# 1_IIP_Charge.net
KiCad netlist of a schematic drawn in Altium Designer
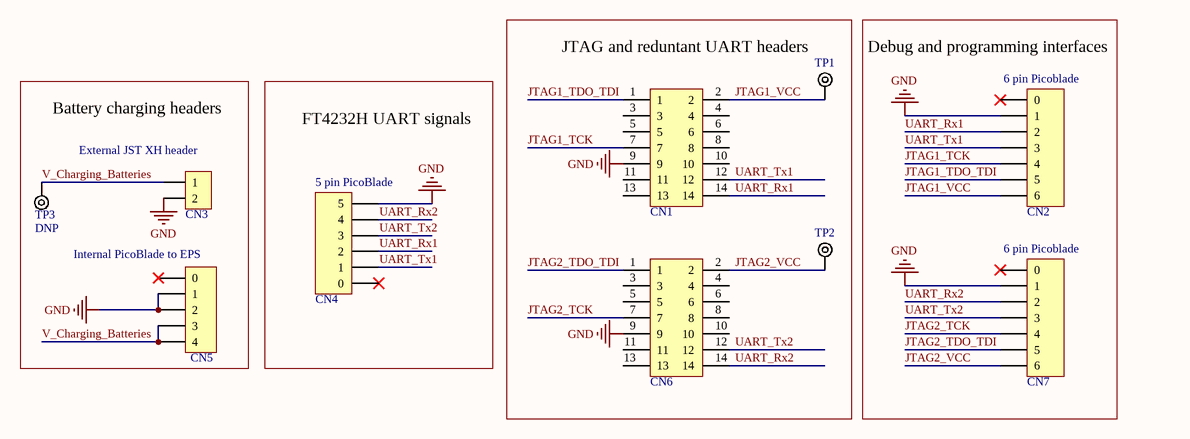
[diagram p0: 1_IIP_Charge.SchDoc]

(export (version "E")
  (design (tool "Eeschema 10.0.6"))
  (components
    (comp (ref "CN1")
      (value "7 POS dual line Pin Header 2.54mm")
      (footprint "CONN HEADER VERT 14POS 2.54MM")
      (description "Headers & Wire Housings 07+07 DIL VERTICAL PIN HEADER GOLD HT")
      (fields (field (name "MANUFACTURER") "Harwin") (field (name "MANUFACTURER PART NUMBER") "M20-9980745"))
      (libsource (lib "IB_floripasat2") (part "M20-9980745"))
    )
    (comp (ref "CN2")
      (value "6 pin Picoblade")
      (footprint "PICO BLADE 0533980671")
      (description "1.25mm Pitch PicoBlade™ Header, Surface Mount, Vertical, 6 Circuits")
      (fields (field (name "MANUFACTURER") "Molex") (field (name "MANUFACTURER PART NUMBER") "53398-0671"))
      (libsource (lib "IB_floripasat2") (part "53398-0671"))
    )
    (comp (ref "CN3")
      (value "JST 2 position header 2.5mm")
      (footprint "B2B-XH-A-M(LF)(SN)")
      (description "CONN HEADER TOP 2POS 2.5MM GRN")
      (fields
        (field (name "MANUFACTURER") "JST")
        (field (name "MANUFACTURER PART NUMBER") "B2B-XH-A-M(LF)(SN)")
      )
      (libsource (lib "IB_floripasat2") (part "B2B-XH-A-M(LF)(SN)"))
    )
    (comp (ref "CN4")
      (value "5 pin PicoBlade")
      (footprint "PICO BLADE 0533980571")
      (description "Wire-To-Board Connector, Vertical, PicoBlade 53398 Series, Surface Mount, Header, 5, 1.25 mm")
      (fields (field (name "MANUFACTURER") "Molex") (field (name "MANUFACTURER PART NUMBER") "53398-0571"))
      (libsource (lib "IB_floripasat2") (part "53398-0571"))
    )
    (comp (ref "CN5")
      (value "4 pin Picoblade")
      (footprint "PICO BLADE 0533980471")
      (description "Conn Wire to Board HDR 4 POS 1.25mm Solder ST SMD Embossed T/R")
      (fields (field (name "MANUFACTURER") "Molex"))
      (libsource (lib "IB_floripasat2") (part "0533980471"))
    )
    (comp (ref "CN6")
      (value "7 POS dual line Pin Header 2.54mm")
      (footprint "CONN HEADER VERT 14POS 2.54MM")
      (description "Headers & Wire Housings 07+07 DIL VERTICAL PIN HEADER GOLD HT")
      (fields (field (name "MANUFACTURER") "Harwin") (field (name "MANUFACTURER PART NUMBER") "M20-9980745"))
      (libsource (lib "IB_floripasat2") (part "M20-9980745"))
    )
    (comp (ref "CN7")
      (value "6 pin Picoblade")
      (footprint "PICO BLADE 0533980671")
      (description "1.25mm Pitch PicoBlade™ Header, Surface Mount, Vertical, 6 Circuits")
      (fields (field (name "MANUFACTURER") "Molex") (field (name "MANUFACTURER PART NUMBER") "53398-0671"))
      (libsource (lib "IB_floripasat2") (part "53398-0671"))
    )
    (comp (ref "TP1")
      (value "DNP")
      (footprint "TEST POINT PTH")
      (description "TEST POINT PAD")
      (libsource (lib "IB_floripasat2") (part "Test Point PTH"))
    )
    (comp (ref "TP2")
      (value "DNP")
      (footprint "TEST POINT PTH")
      (description "TEST POINT PAD")
      (libsource (lib "IB_floripasat2") (part "Test Point PTH"))
    )
    (comp (ref "TP3")
      (value "DNP")
      (footprint "TEST POINT PTH")
      (description "TEST POINT PAD")
      (libsource (lib "IB_floripasat2") (part "Test Point PTH"))
    )
  )
  (nets
    (net (code "1") (name "/JTAG1_TCK") (class "Default")
      (node (ref "CN1") (pin "7") (pinfunction "7_7") (pintype "passive"))
      (node (ref "CN2") (pin "4") (pinfunction "4_4") (pintype "passive"))
    )
    (net (code "2") (name "/JTAG1_TDO_TDI") (class "Default")
      (node (ref "CN1") (pin "1") (pinfunction "1_1") (pintype "passive"))
      (node (ref "CN2") (pin "5") (pinfunction "5_5") (pintype "passive"))
    )
    (net (code "3") (name "/JTAG1_VCC") (class "Default")
      (node (ref "CN1") (pin "2") (pinfunction "2_2") (pintype "passive"))
      (node (ref "CN2") (pin "6") (pinfunction "6_6") (pintype "passive"))
      (node (ref "TP1") (pin "1") (pinfunction "1_1") (pintype "passive"))
    )
    (net (code "4") (name "/JTAG2_TCK") (class "Default")
      (node (ref "CN6") (pin "7") (pinfunction "7_7") (pintype "passive"))
      (node (ref "CN7") (pin "4") (pinfunction "4_4") (pintype "passive"))
    )
    (net (code "5") (name "/JTAG2_TDO_TDI") (class "Default")
      (node (ref "CN6") (pin "1") (pinfunction "1_1") (pintype "passive"))
      (node (ref "CN7") (pin "5") (pinfunction "5_5") (pintype "passive"))
    )
    (net (code "6") (name "/JTAG2_VCC") (class "Default")
      (node (ref "CN6") (pin "2") (pinfunction "2_2") (pintype "passive"))
      (node (ref "CN7") (pin "6") (pinfunction "6_6") (pintype "passive"))
      (node (ref "TP2") (pin "1") (pinfunction "1_1") (pintype "passive"))
    )
    (net (code "7") (name "/UART_Rx1") (class "Default")
      (node (ref "CN1") (pin "14") (pinfunction "14_14") (pintype "passive"))
      (node (ref "CN2") (pin "2") (pinfunction "2_2") (pintype "passive"))
      (node (ref "CN4") (pin "2") (pinfunction "2_2") (pintype "passive"))
    )
    (net (code "8") (name "/UART_Rx2") (class "Default")
      (node (ref "CN4") (pin "4") (pinfunction "4_4") (pintype "passive"))
      (node (ref "CN6") (pin "14") (pinfunction "14_14") (pintype "passive"))
      (node (ref "CN7") (pin "2") (pinfunction "2_2") (pintype "passive"))
    )
    (net (code "9") (name "/UART_Tx1") (class "Default")
      (node (ref "CN1") (pin "12") (pinfunction "12_12") (pintype "passive"))
      (node (ref "CN2") (pin "3") (pinfunction "3_3") (pintype "passive"))
      (node (ref "CN4") (pin "1") (pinfunction "1_1") (pintype "passive"))
    )
    (net (code "10") (name "/UART_Tx2") (class "Default")
      (node (ref "CN4") (pin "3") (pinfunction "3_3") (pintype "passive"))
      (node (ref "CN6") (pin "12") (pinfunction "12_12") (pintype "passive"))
      (node (ref "CN7") (pin "3") (pinfunction "3_3") (pintype "passive"))
    )
    (net (code "11") (name "/V_Charging_Batteries") (class "Default")
      (node (ref "CN3") (pin "1") (pinfunction "1_1") (pintype "passive"))
      (node (ref "CN5") (pin "3") (pinfunction "3_3") (pintype "passive"))
      (node (ref "CN5") (pin "4") (pinfunction "4_4") (pintype "passive"))
      (node (ref "TP3") (pin "1") (pinfunction "1_1") (pintype "passive"))
    )
    (net (code "12") (name "GND") (class "Default")
      (node (ref "CN1") (pin "9") (pinfunction "9_9") (pintype "passive"))
      (node (ref "CN2") (pin "1") (pinfunction "1_1") (pintype "passive"))
      (node (ref "CN3") (pin "2") (pinfunction "2_2") (pintype "passive"))
      (node (ref "CN4") (pin "5") (pinfunction "5_5") (pintype "passive"))
      (node (ref "CN5") (pin "1") (pinfunction "1_1") (pintype "passive"))
      (node (ref "CN5") (pin "2") (pinfunction "2_2") (pintype "passive"))
      (node (ref "CN6") (pin "9") (pinfunction "9_9") (pintype "passive"))
      (node (ref "CN7") (pin "1") (pinfunction "1_1") (pintype "passive"))
    )
    (net (code "13") (name "unconnected-(CN1-Pad3)") (class "Default")
      (node (ref "CN1") (pin "3") (pinfunction "3_3") (pintype "passive"))
    )
    (net (code "14") (name "unconnected-(CN1-Pad4)") (class "Default")
      (node (ref "CN1") (pin "4") (pinfunction "4_4") (pintype "passive"))
    )
    (net (code "15") (name "unconnected-(CN1-Pad5)") (class "Default")
      (node (ref "CN1") (pin "5") (pinfunction "5_5") (pintype "passive"))
    )
    (net (code "16") (name "unconnected-(CN1-Pad6)") (class "Default")
      (node (ref "CN1") (pin "6") (pinfunction "6_6") (pintype "passive"))
    )
    (net (code "17") (name "unconnected-(CN1-Pad8)") (class "Default")
      (node (ref "CN1") (pin "8") (pinfunction "8_8") (pintype "passive"))
    )
    (net (code "18") (name "unconnected-(CN1-Pad10)") (class "Default")
      (node (ref "CN1") (pin "10") (pinfunction "10_10") (pintype "passive"))
    )
    (net (code "19") (name "unconnected-(CN1-Pad11)") (class "Default")
      (node (ref "CN1") (pin "11") (pinfunction "11_11") (pintype "passive"))
    )
    (net (code "20") (name "unconnected-(CN1-Pad13)") (class "Default")
      (node (ref "CN1") (pin "13") (pinfunction "13_13") (pintype "passive"))
    )
    (net (code "21") (name "unconnected-(CN2-Pad0)") (class "Default")
      (node (ref "CN2") (pin "0") (pinfunction "0_0") (pintype "passive+no_connect"))
    )
    (net (code "22") (name "unconnected-(CN4-Pad0)") (class "Default")
      (node (ref "CN4") (pin "0") (pinfunction "0_0") (pintype "passive+no_connect"))
    )
    (net (code "23") (name "unconnected-(CN5-Pad0)") (class "Default")
      (node (ref "CN5") (pin "0") (pinfunction "0_0") (pintype "passive+no_connect"))
    )
    (net (code "24") (name "unconnected-(CN6-Pad3)") (class "Default")
      (node (ref "CN6") (pin "3") (pinfunction "3_3") (pintype "passive"))
    )
    (net (code "25") (name "unconnected-(CN6-Pad4)") (class "Default")
      (node (ref "CN6") (pin "4") (pinfunction "4_4") (pintype "passive"))
    )
    (net (code "26") (name "unconnected-(CN6-Pad5)") (class "Default")
      (node (ref "CN6") (pin "5") (pinfunction "5_5") (pintype "passive"))
    )
    (net (code "27") (name "unconnected-(CN6-Pad6)") (class "Default")
      (node (ref "CN6") (pin "6") (pinfunction "6_6") (pintype "passive"))
    )
    (net (code "28") (name "unconnected-(CN6-Pad8)") (class "Default")
      (node (ref "CN6") (pin "8") (pinfunction "8_8") (pintype "passive"))
    )
    (net (code "29") (name "unconnected-(CN6-Pad10)") (class "Default")
      (node (ref "CN6") (pin "10") (pinfunction "10_10") (pintype "passive"))
    )
    (net (code "30") (name "unconnected-(CN6-Pad11)") (class "Default")
      (node (ref "CN6") (pin "11") (pinfunction "11_11") (pintype "passive"))
    )
    (net (code "31") (name "unconnected-(CN6-Pad13)") (class "Default")
      (node (ref "CN6") (pin "13") (pinfunction "13_13") (pintype "passive"))
    )
    (net (code "32") (name "unconnected-(CN7-Pad0)") (class "Default")
      (node (ref "CN7") (pin "0") (pinfunction "0_0") (pintype "passive+no_connect"))
    )
  )
)
